# kuechenlicht.net
KiCad netlist of a schematic drawn in EAGLE
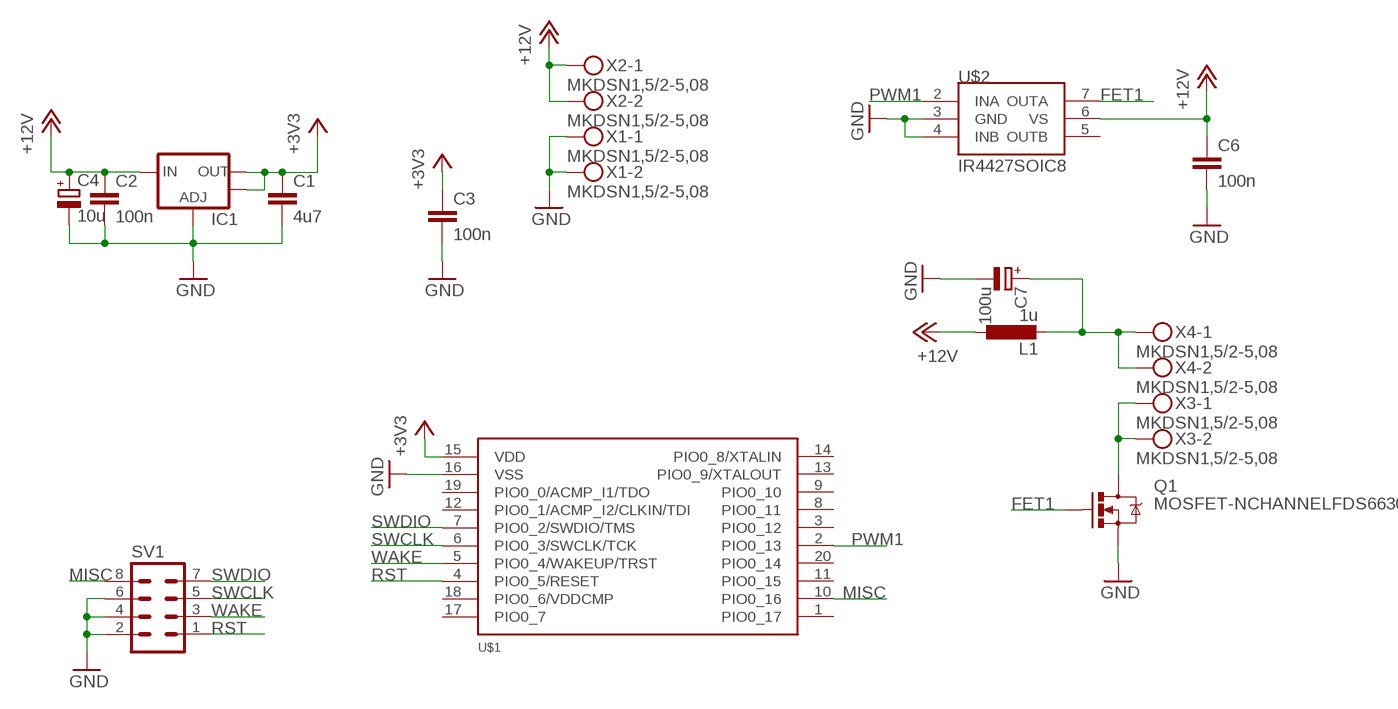
[diagram p0: schematic, sheet 1]

(export (version "E")
  (design (tool "Eeschema 10.0.6"))
  (components
    (comp (ref "C1")
      (value "4u7")
      (footprint "eagle-import:C0805")
      (libsource (lib "eagle-import") (part "C-EUC0805"))
    )
    (comp (ref "C2")
      (value "100n")
      (footprint "eagle-import:C0805")
      (libsource (lib "eagle-import") (part "C-EUC0805"))
    )
    (comp (ref "C3")
      (value "100n")
      (footprint "eagle-import:C0805")
      (libsource (lib "eagle-import") (part "C-EUC0805"))
    )
    (comp (ref "C4")
      (value "10u")
      (footprint "eagle-import:E2,5-6")
      (libsource (lib "eagle-import") (part "rcl_CPOL-EUE2.5-6"))
    )
    (comp (ref "C6")
      (value "100n")
      (footprint "eagle-import:C0805")
      (libsource (lib "eagle-import") (part "C-EUC0805"))
    )
    (comp (ref "C7")
      (value "100u")
      (footprint "eagle-import:PANASONIC_D-BIGPAD")
      (libsource (lib "eagle-import") (part "CPOL-EUPANASONIC_D-BIGPAD"))
    )
    (comp (ref "IC1")
      (value "V_REG_LM1117SOT223")
      (footprint "eagle-import:SOT223")
      (libsource (lib "eagle-import") (part "V_REG_LM1117SOT223"))
    )
    (comp (ref "L1")
      (value "1u")
      (footprint "eagle-import:PISR-BIGPAD")
      (libsource (lib "eagle-import") (part "L-EUPISR-BIGPAD"))
    )
    (comp (ref "Q1")
      (value "MOSFET-NCHANNELFDS6630A")
      (footprint "eagle-import:SO08")
      (libsource (lib "eagle-import") (part "MOSFET-NCHANNELFDS6630A"))
    )
    (comp (ref "SV1")
      (value "MA04-2")
      (footprint "eagle-import:MA04-2")
      (libsource (lib "eagle-import") (part "MA04-2"))
    )
    (comp (ref "U$1")
      (value "LPC812M101JD20")
      (footprint "eagle-import:SOIC20WIDE")
      (libsource (lib "eagle-import") (part "LPC812M101JD20"))
    )
    (comp (ref "U$2")
      (value "IR4427SOIC8")
      (footprint "eagle-import:SOIC8")
      (libsource (lib "eagle-import") (part "IR4427SOIC8"))
    )
    (comp (ref "X1")
      (value "MKDSN1,5/2-5,08")
      (footprint "eagle-import:MKDSN1,5_2-5,08")
      (fields (field (name "MPN") "MKDSN 1,5/2-5.08"))
      (libsource (lib "eagle-import") (part "MKDSN1,5/2-5,08"))
    )
    (comp (ref "X2")
      (value "MKDSN1,5/2-5,08")
      (footprint "eagle-import:MKDSN1,5_2-5,08")
      (fields (field (name "MPN") "MKDSN 1,5/2-5.08"))
      (libsource (lib "eagle-import") (part "MKDSN1,5/2-5,08"))
    )
    (comp (ref "X3")
      (value "MKDSN1,5/2-5,08")
      (footprint "eagle-import:MKDSN1,5_2-5,08")
      (fields (field (name "MPN") "MKDSN 1,5/2-5.08"))
      (libsource (lib "eagle-import") (part "MKDSN1,5/2-5,08"))
    )
    (comp (ref "X4")
      (value "MKDSN1,5/2-5,08")
      (footprint "eagle-import:MKDSN1,5_2-5,08")
      (fields (field (name "MPN") "MKDSN 1,5/2-5.08"))
      (libsource (lib "eagle-import") (part "MKDSN1,5/2-5,08"))
    )
  )
  (nets
    (net (code "1") (name "+3V3") (class "Default")
      (node (ref "C1") (pin "1") (pinfunction "1_1") (pintype "passive"))
      (node (ref "C3") (pin "1") (pinfunction "1_1") (pintype "passive"))
      (node (ref "IC1") (pin "2") (pinfunction "OUT_2") (pintype "output"))
      (node (ref "IC1") (pin "4") (pinfunction "OUT_4") (pintype "output"))
      (node (ref "U$1") (pin "15") (pinfunction "VDD_15") (pintype "bidirectional"))
    )
    (net (code "2") (name "+12V") (class "Default")
      (node (ref "C2") (pin "1") (pinfunction "1_1") (pintype "passive"))
      (node (ref "C4") (pin "+") (pinfunction "+_+") (pintype "passive"))
      (node (ref "C6") (pin "1") (pinfunction "1_1") (pintype "passive"))
      (node (ref "IC1") (pin "3") (pinfunction "IN_3") (pintype "input"))
      (node (ref "L1") (pin "1") (pinfunction "1_1") (pintype "passive"))
      (node (ref "U$2") (pin "6") (pinfunction "VS_6") (pintype "bidirectional"))
      (node (ref "X2") (pin "1") (pinfunction "KL_1") (pintype "passive"))
      (node (ref "X2") (pin "2") (pinfunction "KL_2") (pintype "passive"))
    )
    (net (code "3") (name "/FET1") (class "Default")
      (node (ref "Q1") (pin "4") (pinfunction "G_4") (pintype "passive"))
      (node (ref "U$2") (pin "7") (pinfunction "OUTA_7") (pintype "bidirectional"))
    )
    (net (code "4") (name "/MISC") (class "Default")
      (node (ref "SV1") (pin "8") (pinfunction "8_8") (pintype "passive"))
      (node (ref "U$1") (pin "10") (pinfunction "PIO0_16_10") (pintype "bidirectional"))
    )
    (net (code "5") (name "/PWM1") (class "Default")
      (node (ref "U$1") (pin "2") (pinfunction "PIO0_13_2") (pintype "bidirectional"))
      (node (ref "U$2") (pin "2") (pinfunction "INA_2") (pintype "bidirectional"))
    )
    (net (code "6") (name "/RST") (class "Default")
      (node (ref "SV1") (pin "1") (pinfunction "1_1") (pintype "passive"))
      (node (ref "U$1") (pin "4") (pinfunction "PIO0_5/RESET_4") (pintype "bidirectional"))
    )
    (net (code "7") (name "/SWCLK") (class "Default")
      (node (ref "SV1") (pin "5") (pinfunction "5_5") (pintype "passive"))
      (node (ref "U$1") (pin "6") (pinfunction "PIO0_3/SWCLK/TCK_6") (pintype "bidirectional"))
    )
    (net (code "8") (name "/SWDIO") (class "Default")
      (node (ref "SV1") (pin "7") (pinfunction "7_7") (pintype "passive"))
      (node (ref "U$1") (pin "7") (pinfunction "PIO0_2/SWDIO/TMS_7") (pintype "bidirectional"))
    )
    (net (code "9") (name "/WAKE") (class "Default")
      (node (ref "SV1") (pin "3") (pinfunction "3_3") (pintype "passive"))
      (node (ref "U$1") (pin "5") (pinfunction "PIO0_4/WAKEUP/TRST_5") (pintype "bidirectional"))
    )
    (net (code "10") (name "GND") (class "Default")
      (node (ref "C1") (pin "2") (pinfunction "2_2") (pintype "passive"))
      (node (ref "C2") (pin "2") (pinfunction "2_2") (pintype "passive"))
      (node (ref "C3") (pin "2") (pinfunction "2_2") (pintype "passive"))
      (node (ref "C4") (pin "-") (pinfunction "-_-") (pintype "passive"))
      (node (ref "C6") (pin "2") (pinfunction "2_2") (pintype "passive"))
      (node (ref "C7") (pin "-") (pinfunction "-_-") (pintype "passive"))
      (node (ref "IC1") (pin "1") (pinfunction "ADJ_1") (pintype "input"))
      (node (ref "Q1") (pin "1") (pinfunction "S_1") (pintype "passive"))
      (node (ref "Q1") (pin "2") (pinfunction "S_2") (pintype "passive"))
      (node (ref "Q1") (pin "3") (pinfunction "S_3") (pintype "passive"))
      (node (ref "SV1") (pin "2") (pinfunction "2_2") (pintype "passive"))
      (node (ref "SV1") (pin "4") (pinfunction "4_4") (pintype "passive"))
      (node (ref "SV1") (pin "6") (pinfunction "6_6") (pintype "passive"))
      (node (ref "U$1") (pin "16") (pinfunction "VSS_16") (pintype "bidirectional"))
      (node (ref "U$2") (pin "3") (pinfunction "GND_3") (pintype "bidirectional"))
      (node (ref "U$2") (pin "4") (pinfunction "INB_4") (pintype "bidirectional"))
      (node (ref "X1") (pin "1") (pinfunction "KL_1") (pintype "passive"))
      (node (ref "X1") (pin "2") (pinfunction "KL_2") (pintype "passive"))
    )
    (net (code "11") (name "Net-(X3A-KL)") (class "Default")
      (node (ref "Q1") (pin "5") (pinfunction "D_5") (pintype "passive"))
      (node (ref "Q1") (pin "6") (pinfunction "D_6") (pintype "passive"))
      (node (ref "Q1") (pin "7") (pinfunction "D_7") (pintype "passive"))
      (node (ref "Q1") (pin "8") (pinfunction "D_8") (pintype "passive"))
      (node (ref "X3") (pin "1") (pinfunction "KL_1") (pintype "passive"))
      (node (ref "X3") (pin "2") (pinfunction "KL_2") (pintype "passive"))
    )
    (net (code "12") (name "Net-(X4A-KL)") (class "Default")
      (node (ref "C7") (pin "+") (pinfunction "+_+") (pintype "passive"))
      (node (ref "L1") (pin "2") (pinfunction "2_2") (pintype "passive"))
      (node (ref "X4") (pin "1") (pinfunction "KL_1") (pintype "passive"))
      (node (ref "X4") (pin "2") (pinfunction "KL_2") (pintype "passive"))
    )
    (net (code "13") (name "unconnected-(U$1-PIO0_0{slash}ACMP_I1{slash}TDO-Pad19)") (class "Default")
      (node (ref "U$1") (pin "19") (pinfunction "PIO0_0/ACMP_I1/TDO_19") (pintype "bidirectional"))
    )
    (net (code "14") (name "unconnected-(U$1-PIO0_1{slash}ACMP_I2{slash}CLKIN{slash}TDI-Pad12)") (class "Default")
      (node (ref "U$1") (pin "12") (pinfunction "PIO0_1/ACMP_I2/CLKIN/TDI_12") (pintype "bidirectional"))
    )
    (net (code "15") (name "unconnected-(U$1-PIO0_6{slash}VDDCMP-Pad18)") (class "Default")
      (node (ref "U$1") (pin "18") (pinfunction "PIO0_6/VDDCMP_18") (pintype "bidirectional"))
    )
    (net (code "16") (name "unconnected-(U$1-PIO0_7-Pad17)") (class "Default")
      (node (ref "U$1") (pin "17") (pinfunction "PIO0_7_17") (pintype "bidirectional"))
    )
    (net (code "17") (name "unconnected-(U$1-PIO0_8{slash}XTALIN-Pad14)") (class "Default")
      (node (ref "U$1") (pin "14") (pinfunction "PIO0_8/XTALIN_14") (pintype "bidirectional"))
    )
    (net (code "18") (name "unconnected-(U$1-PIO0_9{slash}XTALOUT-Pad13)") (class "Default")
      (node (ref "U$1") (pin "13") (pinfunction "PIO0_9/XTALOUT_13") (pintype "bidirectional"))
    )
    (net (code "19") (name "unconnected-(U$1-PIO0_10-Pad9)") (class "Default")
      (node (ref "U$1") (pin "9") (pinfunction "PIO0_10_9") (pintype "bidirectional"))
    )
    (net (code "20") (name "unconnected-(U$1-PIO0_11-Pad8)") (class "Default")
      (node (ref "U$1") (pin "8") (pinfunction "PIO0_11_8") (pintype "bidirectional"))
    )
    (net (code "21") (name "unconnected-(U$1-PIO0_12-Pad3)") (class "Default")
      (node (ref "U$1") (pin "3") (pinfunction "PIO0_12_3") (pintype "bidirectional"))
    )
    (net (code "22") (name "unconnected-(U$1-PIO0_14-Pad20)") (class "Default")
      (node (ref "U$1") (pin "20") (pinfunction "PIO0_14_20") (pintype "bidirectional"))
    )
    (net (code "23") (name "unconnected-(U$1-PIO0_15-Pad11)") (class "Default")
      (node (ref "U$1") (pin "11") (pinfunction "PIO0_15_11") (pintype "bidirectional"))
    )
    (net (code "24") (name "unconnected-(U$1-PIO0_17-Pad1)") (class "Default")
      (node (ref "U$1") (pin "1") (pinfunction "PIO0_17_1") (pintype "bidirectional"))
    )
    (net (code "25") (name "unconnected-(U$2-OUTB-Pad5)") (class "Default")
      (node (ref "U$2") (pin "5") (pinfunction "OUTB_5") (pintype "bidirectional"))
    )
  )
)
